# Signal_from_sunrise.net
KiCad netlist of a schematic drawn in EAGLE
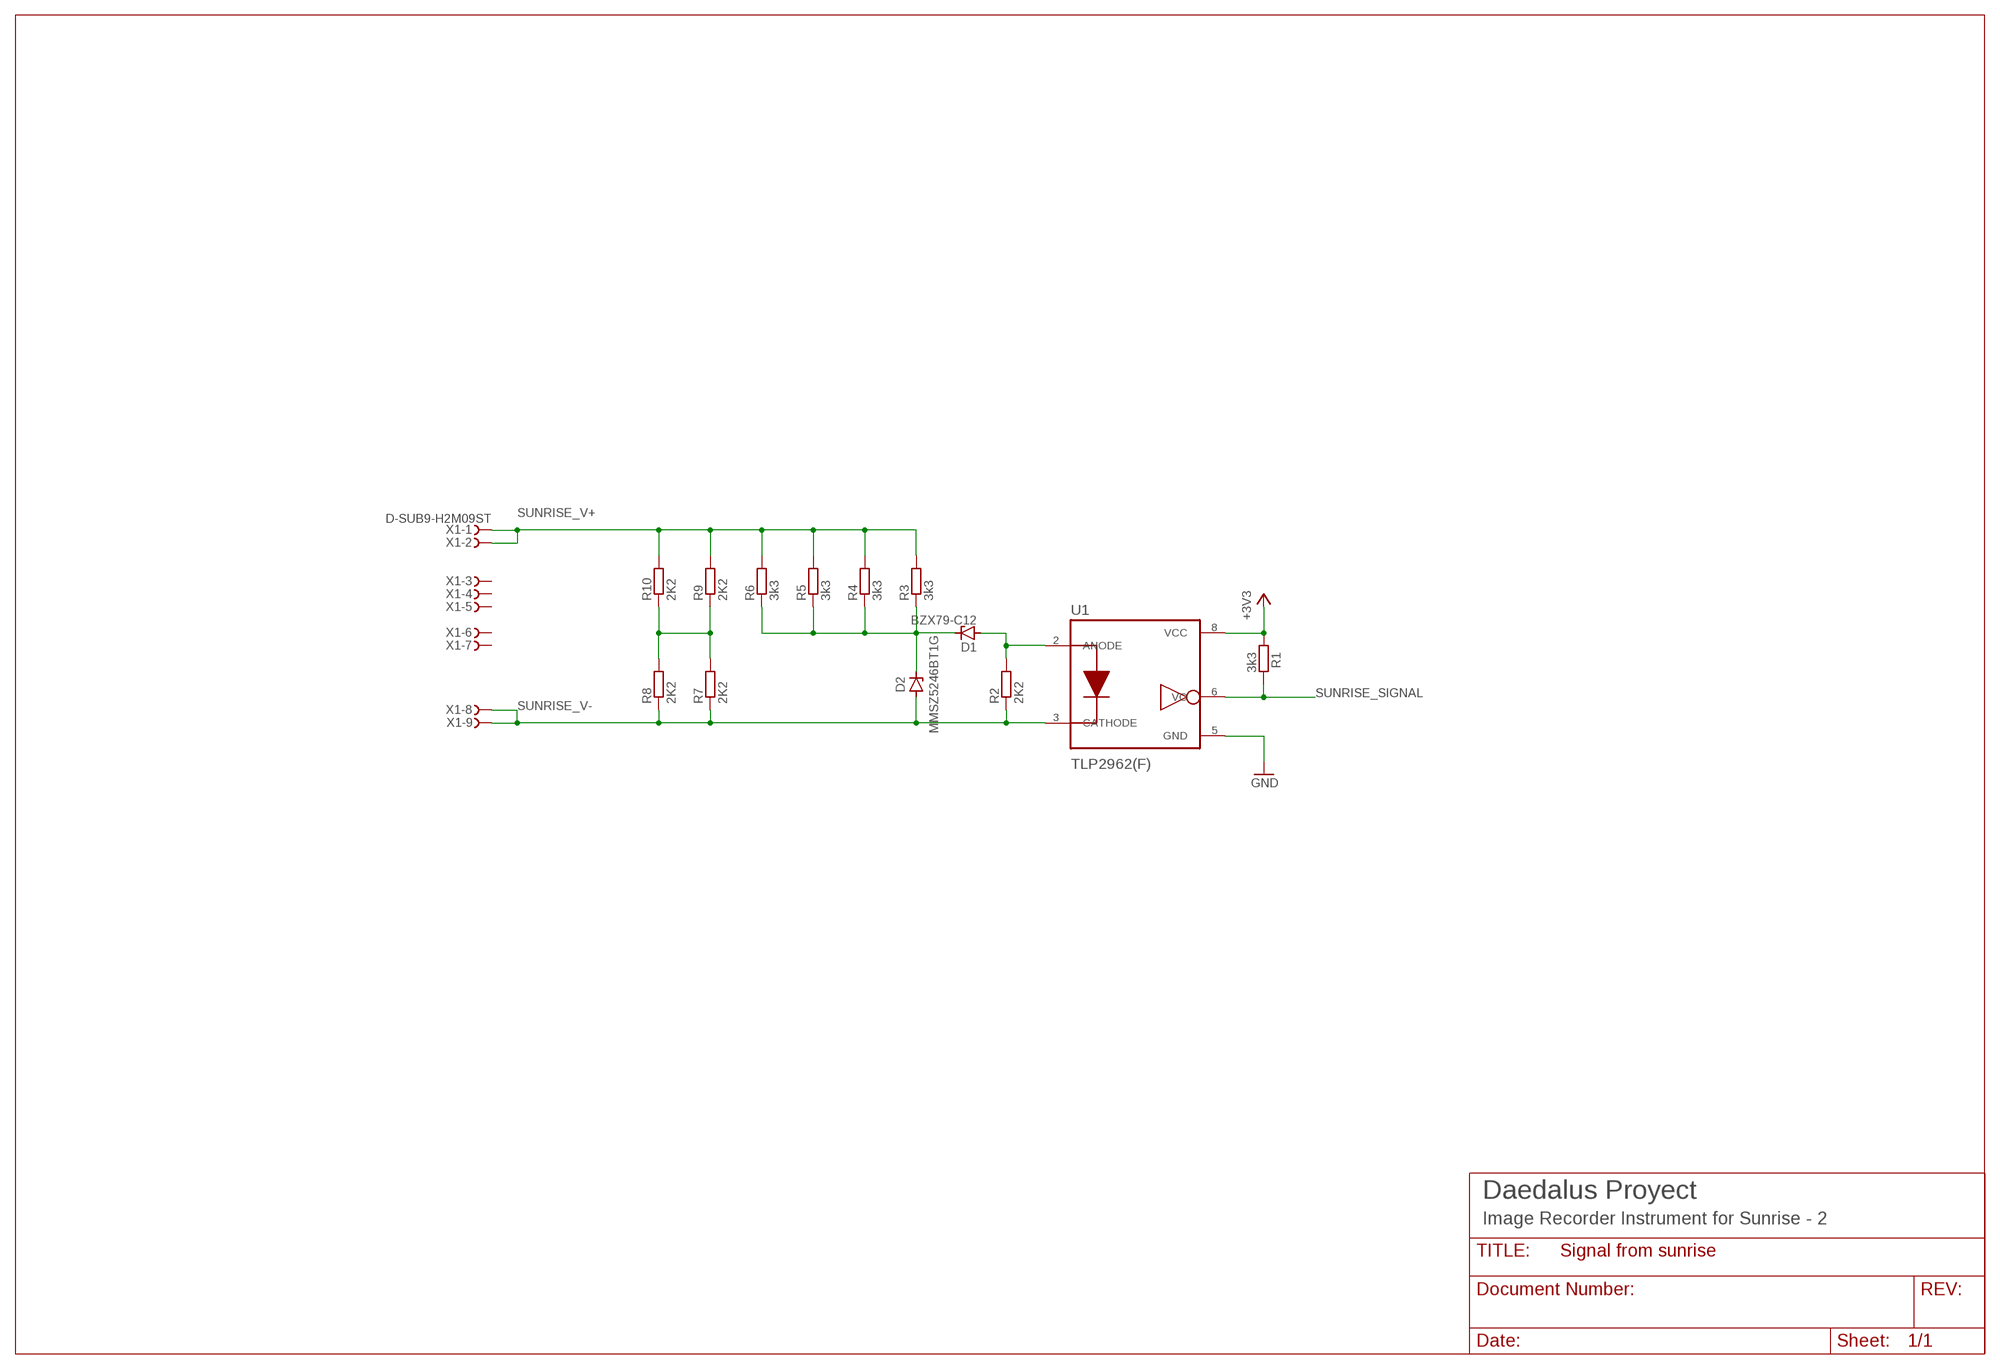
[diagram p0: schematic, sheet 1]

(export (version "E")
  (design (tool "Eeschema 10.0.6"))
  (components
    (comp (ref "D1")
      (value "BZX79-C12")
      (footprint "eagle-import:DO35Z10")
      (libsource (lib "eagle-import") (part "BZX55"))
    )
    (comp (ref "D2")
      (value "MMSZ5246BT1G")
      (footprint "eagle-import:SODFL3718X115")
      (fields (field (name "MANUFACTURER") "ON Semiconductor ") (field (name "MPN") "MMSZ5240BT1G"))
      (libsource (lib "eagle-import") (part "ZENER_DO-219-AB(SOD123F)MMSZ5240BT"))
    )
    (comp (ref "R1")
      (value "3k3")
      (footprint "eagle-import:R1206")
      (libsource (lib "eagle-import") (part "R-EU_R1206"))
    )
    (comp (ref "R2")
      (value "2K2")
      (footprint "eagle-import:R1206")
      (libsource (lib "eagle-import") (part "R-EU_R1206"))
    )
    (comp (ref "R3")
      (value "3k3")
      (footprint "eagle-import:R1206")
      (libsource (lib "eagle-import") (part "R-EU_R1206"))
    )
    (comp (ref "R4")
      (value "3k3")
      (footprint "eagle-import:R1206")
      (libsource (lib "eagle-import") (part "R-EU_R1206"))
    )
    (comp (ref "R5")
      (value "3k3")
      (footprint "eagle-import:R1206")
      (libsource (lib "eagle-import") (part "R-EU_R1206"))
    )
    (comp (ref "R6")
      (value "3k3")
      (footprint "eagle-import:R1206")
      (libsource (lib "eagle-import") (part "R-EU_R1206"))
    )
    (comp (ref "R7")
      (value "2K2")
      (footprint "eagle-import:R1206")
      (libsource (lib "eagle-import") (part "R-EU_R1206"))
    )
    (comp (ref "R8")
      (value "2K2")
      (footprint "eagle-import:R1206")
      (libsource (lib "eagle-import") (part "R-EU_R1206"))
    )
    (comp (ref "R9")
      (value "2K2")
      (footprint "eagle-import:R1206")
      (libsource (lib "eagle-import") (part "R-EU_R1206"))
    )
    (comp (ref "R10")
      (value "2K2")
      (footprint "eagle-import:R1206")
      (libsource (lib "eagle-import") (part "R-EU_R1206"))
    )
    (comp (ref "U1")
      (value "TLP2962(F)")
      (footprint "eagle-import:DIP762W50P254L1018H450Q8")
      (fields (field (name "MF") "Toshiba Semiconductor"))
      (libsource (lib "eagle-import") (part "TLP2962(F)"))
    )
    (comp (ref "X1")
      (value "D-SUB9-H2M09ST")
      (footprint "eagle-import:H2M09ST")
      (libsource (lib "eagle-import") (part "D-SUB9-H2M09ST"))
    )
  )
  (nets
    (net (code "1") (name "+3V3") (class "Default")
      (node (ref "R1") (pin "1") (pinfunction "1_1") (pintype "passive"))
      (node (ref "U1") (pin "8") (pinfunction "VCC_8") (pintype "power_in"))
    )
    (net (code "2") (name "/SUNRISE_SIGNAL") (class "Default")
      (node (ref "R1") (pin "2") (pinfunction "2_2") (pintype "passive"))
      (node (ref "U1") (pin "6") (pinfunction "VO_6") (pintype "output"))
    )
    (net (code "3") (name "/SUNRISE_V+") (class "Default")
      (node (ref "R10") (pin "2") (pinfunction "2_2") (pintype "passive"))
      (node (ref "R3") (pin "2") (pinfunction "2_2") (pintype "passive"))
      (node (ref "R4") (pin "2") (pinfunction "2_2") (pintype "passive"))
      (node (ref "R5") (pin "2") (pinfunction "2_2") (pintype "passive"))
      (node (ref "R6") (pin "2") (pinfunction "2_2") (pintype "passive"))
      (node (ref "R9") (pin "2") (pinfunction "2_2") (pintype "passive"))
      (node (ref "X1") (pin "1") (pinfunction "F_1") (pintype "passive"))
      (node (ref "X1") (pin "2") (pinfunction "F_2") (pintype "passive"))
    )
    (net (code "4") (name "/SUNRISE_V-") (class "Default")
      (node (ref "D2") (pin "2") (pinfunction "A_2") (pintype "passive"))
      (node (ref "R2") (pin "1") (pinfunction "1_1") (pintype "passive"))
      (node (ref "R7") (pin "1") (pinfunction "1_1") (pintype "passive"))
      (node (ref "R8") (pin "1") (pinfunction "1_1") (pintype "passive"))
      (node (ref "U1") (pin "3") (pinfunction "CATHODE_3") (pintype "bidirectional"))
      (node (ref "X1") (pin "8") (pinfunction "F_8") (pintype "passive"))
      (node (ref "X1") (pin "9") (pinfunction "F_9") (pintype "passive"))
    )
    (net (code "5") (name "GND") (class "Default")
      (node (ref "U1") (pin "5") (pinfunction "GND_5") (pintype "power_in"))
    )
    (net (code "6") (name "Net-(D2-C)") (class "Default")
      (node (ref "D1") (pin "C") (pinfunction "C_C") (pintype "passive"))
      (node (ref "D2") (pin "1") (pinfunction "C_1") (pintype "passive"))
      (node (ref "R3") (pin "1") (pinfunction "1_1") (pintype "passive"))
      (node (ref "R4") (pin "1") (pinfunction "1_1") (pintype "passive"))
      (node (ref "R5") (pin "1") (pinfunction "1_1") (pintype "passive"))
      (node (ref "R6") (pin "1") (pinfunction "1_1") (pintype "passive"))
    )
    (net (code "7") (name "Net-(R10-Pad1)") (class "Default")
      (node (ref "R10") (pin "1") (pinfunction "1_1") (pintype "passive"))
      (node (ref "R7") (pin "2") (pinfunction "2_2") (pintype "passive"))
      (node (ref "R8") (pin "2") (pinfunction "2_2") (pintype "passive"))
      (node (ref "R9") (pin "1") (pinfunction "1_1") (pintype "passive"))
    )
    (net (code "8") (name "Net-(U1-ANODE)") (class "Default")
      (node (ref "D1") (pin "A") (pinfunction "A_A") (pintype "passive"))
      (node (ref "R2") (pin "2") (pinfunction "2_2") (pintype "passive"))
      (node (ref "U1") (pin "2") (pinfunction "ANODE_2") (pintype "bidirectional"))
    )
    (net (code "9") (name "unconnected-(X1C-F-Pad3)") (class "Default")
      (node (ref "X1") (pin "3") (pinfunction "F_3") (pintype "passive"))
    )
    (net (code "10") (name "unconnected-(X1D-F-Pad4)") (class "Default")
      (node (ref "X1") (pin "4") (pinfunction "F_4") (pintype "passive"))
    )
    (net (code "11") (name "unconnected-(X1E-F-Pad5)") (class "Default")
      (node (ref "X1") (pin "5") (pinfunction "F_5") (pintype "passive"))
    )
    (net (code "12") (name "unconnected-(X1F-F-Pad6)") (class "Default")
      (node (ref "X1") (pin "6") (pinfunction "F_6") (pintype "passive"))
    )
    (net (code "13") (name "unconnected-(X1G-F-Pad7)") (class "Default")
      (node (ref "X1") (pin "7") (pinfunction "F_7") (pintype "passive"))
    )
  )
)
